# MASTER.net
KiCad netlist of a schematic drawn in Altium Designer
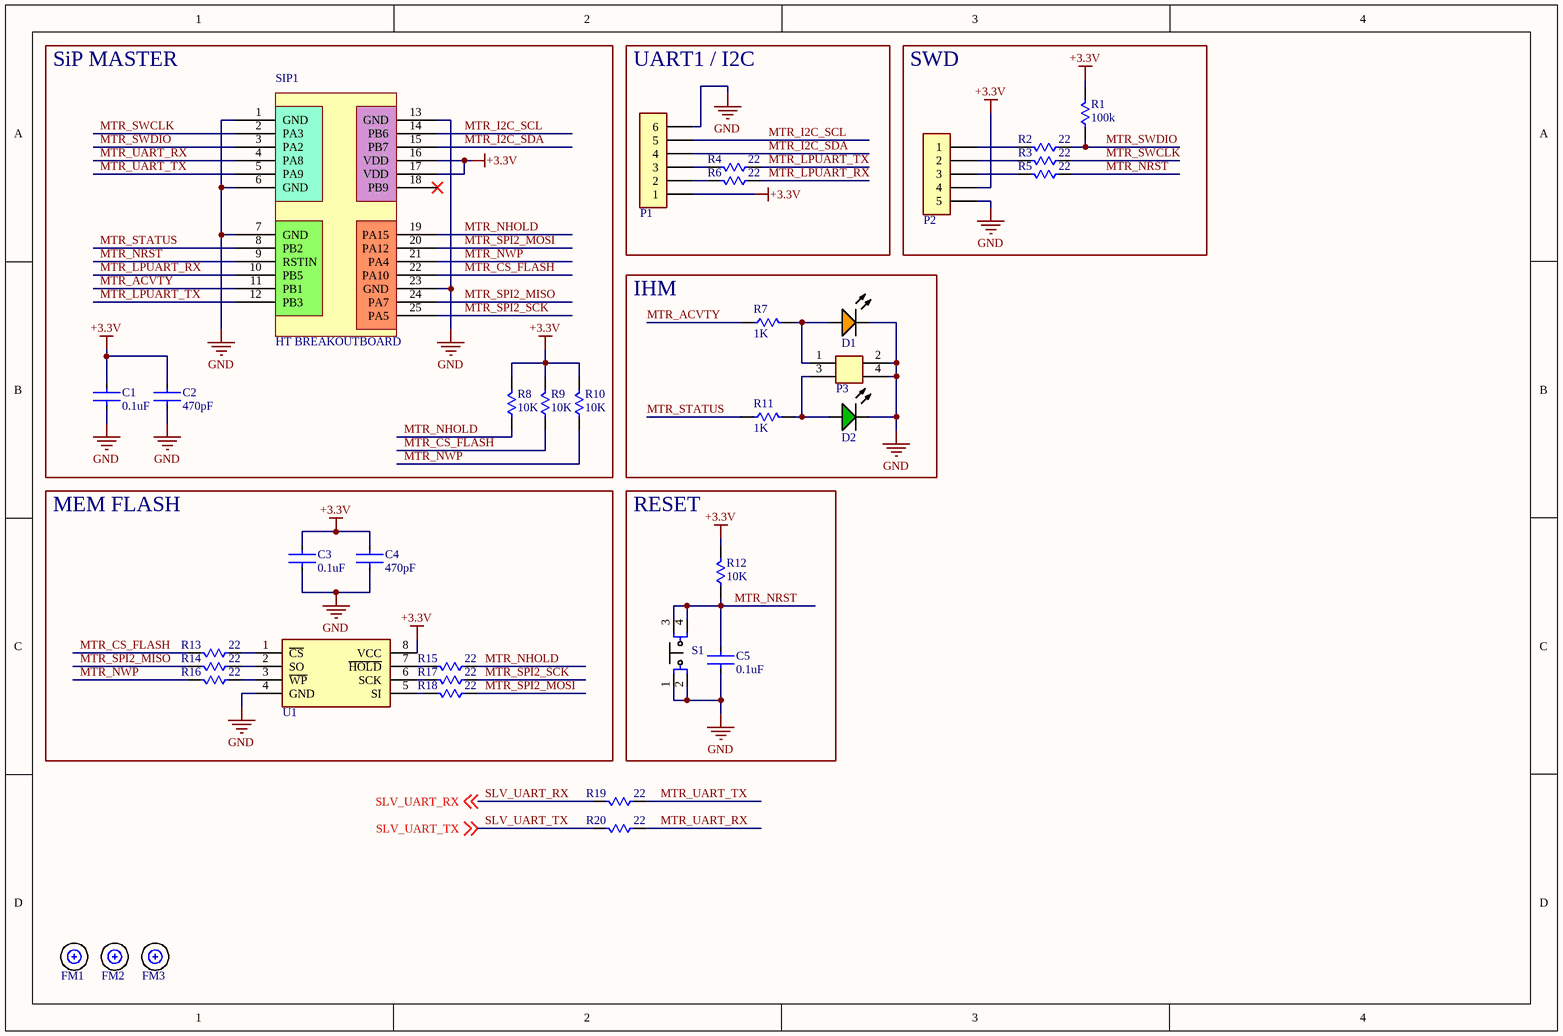
[diagram p0: MASTER.SchDoc]

(export (version "E")
  (design (tool "Eeschema 10.0.6"))
  (components
    (comp (ref "C1")
      (value "0.1uF")
      (footprint "0805-CAP")
      (description "CAP CER SMD 0805, 0.1uF / 16V, ±10%")
      (fields
        (field (name "MANUFACTURER") "Yageo")
        (field (name "MANUFACTURER PART NUMBER") "AC0805KRX7R7BB104")
      )
      (libsource (lib "Capacitor") (part "AC0805KRX7R7BB104"))
    )
    (comp (ref "C2")
      (value "470pF")
      (footprint "0805-CAP")
      (description "CAP CER SMD 0805, 470pF / 100V, ±5% C0G/NP0")
      (fields
        (field (name "MANUFACTURER") "Wurth Electronics")
        (field (name "MANUFACTURER PART NUMBER") "885012007086")
      )
      (libsource (lib "Capacitor") (part "885012007086"))
    )
    (comp (ref "C3")
      (value "0.1uF")
      (footprint "0805-CAP")
      (description "CAP CER SMD 0805, 0.1uF / 16V, ±10%")
      (fields
        (field (name "MANUFACTURER") "Yageo")
        (field (name "MANUFACTURER PART NUMBER") "AC0805KRX7R7BB104")
      )
      (libsource (lib "Capacitor") (part "AC0805KRX7R7BB104"))
    )
    (comp (ref "C4")
      (value "470pF")
      (footprint "0805-CAP")
      (description "CAP CER SMD 0805, 470pF / 100V, ±5% C0G/NP0")
      (fields
        (field (name "MANUFACTURER") "Wurth Electronics")
        (field (name "MANUFACTURER PART NUMBER") "885012007086")
      )
      (libsource (lib "Capacitor") (part "885012007086"))
    )
    (comp (ref "C5")
      (value "0.1uF")
      (footprint "0805-CAP")
      (description "CAP CER SMD 0805, 0.1uF / 16V, ±10%")
      (fields
        (field (name "MANUFACTURER") "Yageo")
        (field (name "MANUFACTURER PART NUMBER") "AC0805KRX7R7BB104")
      )
      (libsource (lib "Capacitor") (part "AC0805KRX7R7BB104"))
    )
    (comp (ref "D1")
      (value "ORANGE")
      (footprint "0805-LED-ORANGE")
      (description "LED ORANGE, SMD 0805, 2.1V/30mA")
      (fields
        (field (name "MANUFACTURER") "Vishay Lite-On")
        (field (name "MANUFACTURER PART NUMBER") "LTST-C170AKT")
      )
      (libsource (lib "Diode") (part "LTST-C170AKT"))
    )
    (comp (ref "D2")
      (value "GREEN")
      (footprint "0805-LED-GREEN")
      (description "LED GREEN, SMD 0805, 2.1V/30mA")
      (fields
        (field (name "MANUFACTURER") "Vishay Lite-On")
        (field (name "MANUFACTURER PART NUMBER") "LTST-C170GKT")
      )
      (libsource (lib "Diode") (part "LTST-C170GKT"))
    )
    (comp (ref "FM1")
      (value "FIDUCIAIS - SMD - POINT")
      (footprint "FIDUCIAL  1mm SMD")
      (libsource (lib "Connector") (part "FIDUCIAIS - SMD - POINT"))
    )
    (comp (ref "FM2")
      (value "FIDUCIAIS - SMD - POINT")
      (footprint "FIDUCIAL  1mm SMD")
      (libsource (lib "Connector") (part "FIDUCIAIS - SMD - POINT"))
    )
    (comp (ref "FM3")
      (value "FIDUCIAIS - SMD - POINT")
      (footprint "FIDUCIAL  1mm SMD")
      (libsource (lib "Connector") (part "FIDUCIAIS - SMD - POINT"))
    )
    (comp (ref "P1")
      (value "75915-306LF")
      (footprint "HEADER_6P_PVF - 75915-306LF")
      (fields (field (name "MANUFACTURER") "Amphenol ICC / FCI"))
      (libsource (lib "Connector") (part "75915-306LF"))
    )
    (comp (ref "P2")
      (value "Header 6")
      (footprint "_HEADER_5P_PVF")
      (fields
        (field (name "MANUFACTURER") "Amphenol ICC / FCI")
        (field (name "MANUFACTURER PART NUMBER") "75915-305LF")
      )
      (libsource (lib "Connector") (part "75915-305LF"))
    )
    (comp (ref "P3")
      (value "_HEADER_2X2_PVM_2.54MM")
      (footprint "67997-404HLF")
      (description "HEADER 2X3, PTH-2.54MM, VERT, MALE")
      (libsource (lib "Connector") (part "_HEADER_2X2_PVM_2.54MM"))
    )
    (comp (ref "R1")
      (value "100k")
      (footprint "0805-RES")
      (description "RES SMD 0805, 100K OHM 5% 1/8W")
      (fields
        (field (name "MANUFACTURER") "Panasonic")
        (field (name "MANUFACTURER PART NUMBER") "ERJ-6GEYJ104V")
      )
      (libsource (lib "Resistor") (part "ERJ-6GEYJ104V"))
    )
    (comp (ref "R2")
      (value "22")
      (footprint "0805-RES")
      (description "RES SMD 0805, 22 OHM 5% 1/4W")
      (fields
        (field (name "MANUFACTURER") "Panasonic")
        (field (name "MANUFACTURER PART NUMBER") "ERJ-P06J220V")
      )
      (libsource (lib "Resistor") (part "ERJ-P06J220V"))
    )
    (comp (ref "R3")
      (value "22")
      (footprint "0805-RES")
      (description "RES SMD 0805, 22 OHM 5% 1/4W")
      (fields
        (field (name "MANUFACTURER") "Panasonic")
        (field (name "MANUFACTURER PART NUMBER") "ERJ-P06J220V")
      )
      (libsource (lib "Resistor") (part "ERJ-P06J220V"))
    )
    (comp (ref "R4")
      (value "22")
      (footprint "0805-RES")
      (description "RES SMD 0805, 22 OHM 5% 1/4W")
      (fields
        (field (name "MANUFACTURER") "Panasonic")
        (field (name "MANUFACTURER PART NUMBER") "ERJ-P06J220V")
      )
      (libsource (lib "Resistor") (part "ERJ-P06J220V"))
    )
    (comp (ref "R5")
      (value "22")
      (footprint "0805-RES")
      (description "RES SMD 0805, 22 OHM 5% 1/4W")
      (fields
        (field (name "MANUFACTURER") "Panasonic")
        (field (name "MANUFACTURER PART NUMBER") "ERJ-P06J220V")
      )
      (libsource (lib "Resistor") (part "ERJ-P06J220V"))
    )
    (comp (ref "R6")
      (value "22")
      (footprint "0805-RES")
      (description "RES SMD 0805, 22 OHM 5% 1/4W")
      (fields
        (field (name "MANUFACTURER") "Panasonic")
        (field (name "MANUFACTURER PART NUMBER") "ERJ-P06J220V")
      )
      (libsource (lib "Resistor") (part "ERJ-P06J220V"))
    )
    (comp (ref "R7")
      (value "1K")
      (footprint "0805-RES")
      (description "Res Thin Film 0805 1K Ohm 1% 0.25W(1/4W) ±100ppm/C Sulfur Resistant Pad SMD T/R")
      (fields
        (field (name "MANUFACTURER") "Stackpole Electronics")
        (field (name "MANUFACTURER PART NUMBER") "RNCP0805FTD1K00")
      )
      (libsource (lib "Resistor") (part "RNCP0805FTD1K00"))
    )
    (comp (ref "R8")
      (value "10K")
      (footprint "0805-RES")
      (description "Res Thin Film 0805 10K Ohm 1% 1/4W ±100ppm/°C Molded SMD Paper T/R")
      (fields
        (field (name "MANUFACTURER") "Stackpole Electronics")
        (field (name "MANUFACTURER PART NUMBER") "RNCP0805FTD10K0")
      )
      (libsource (lib "Resistor") (part "RNCP0805FTD10K0"))
    )
    (comp (ref "R9")
      (value "10K")
      (footprint "0805-RES")
      (description "Res Thin Film 0805 10K Ohm 1% 1/4W ±100ppm/°C Molded SMD Paper T/R")
      (fields
        (field (name "MANUFACTURER") "Stackpole Electronics")
        (field (name "MANUFACTURER PART NUMBER") "RNCP0805FTD10K0")
      )
      (libsource (lib "Resistor") (part "RNCP0805FTD10K0"))
    )
    (comp (ref "R10")
      (value "10K")
      (footprint "0805-RES")
      (description "Res Thin Film 0805 10K Ohm 1% 1/4W ±100ppm/°C Molded SMD Paper T/R")
      (fields
        (field (name "MANUFACTURER") "Stackpole Electronics")
        (field (name "MANUFACTURER PART NUMBER") "RNCP0805FTD10K0")
      )
      (libsource (lib "Resistor") (part "RNCP0805FTD10K0"))
    )
    (comp (ref "R11")
      (value "1K")
      (footprint "0805-RES")
      (description "Res Thin Film 0805 1K Ohm 1% 0.25W(1/4W) ±100ppm/C Sulfur Resistant Pad SMD T/R")
      (fields
        (field (name "MANUFACTURER") "Stackpole Electronics")
        (field (name "MANUFACTURER PART NUMBER") "RNCP0805FTD1K00")
      )
      (libsource (lib "Resistor") (part "RNCP0805FTD1K00"))
    )
    (comp (ref "R12")
      (value "10K")
      (footprint "0805-RES")
      (description "Res Thin Film 0805 10K Ohm 1% 1/4W ±100ppm/°C Molded SMD Paper T/R")
      (fields
        (field (name "MANUFACTURER") "Stackpole Electronics")
        (field (name "MANUFACTURER PART NUMBER") "RNCP0805FTD10K0")
      )
      (libsource (lib "Resistor") (part "RNCP0805FTD10K0"))
    )
    (comp (ref "R13")
      (value "22")
      (footprint "0805-RES")
      (description "RES SMD 0805, 22 OHM 5% 1/4W")
      (fields
        (field (name "MANUFACTURER") "Panasonic")
        (field (name "MANUFACTURER PART NUMBER") "ERJ-P06J220V")
      )
      (libsource (lib "Resistor") (part "ERJ-P06J220V"))
    )
    (comp (ref "R14")
      (value "22")
      (footprint "0805-RES")
      (description "RES SMD 0805, 22 OHM 5% 1/4W")
      (fields
        (field (name "MANUFACTURER") "Panasonic")
        (field (name "MANUFACTURER PART NUMBER") "ERJ-P06J220V")
      )
      (libsource (lib "Resistor") (part "ERJ-P06J220V"))
    )
    (comp (ref "R15")
      (value "22")
      (footprint "0805-RES")
      (description "RES SMD 0805, 22 OHM 5% 1/4W")
      (fields
        (field (name "MANUFACTURER") "Panasonic")
        (field (name "MANUFACTURER PART NUMBER") "ERJ-P06J220V")
      )
      (libsource (lib "Resistor") (part "ERJ-P06J220V"))
    )
    (comp (ref "R16")
      (value "22")
      (footprint "0805-RES")
      (description "RES SMD 0805, 22 OHM 5% 1/4W")
      (fields
        (field (name "MANUFACTURER") "Panasonic")
        (field (name "MANUFACTURER PART NUMBER") "ERJ-P06J220V")
      )
      (libsource (lib "Resistor") (part "ERJ-P06J220V"))
    )
    (comp (ref "R17")
      (value "22")
      (footprint "0805-RES")
      (description "RES SMD 0805, 22 OHM 5% 1/4W")
      (fields
        (field (name "MANUFACTURER") "Panasonic")
        (field (name "MANUFACTURER PART NUMBER") "ERJ-P06J220V")
      )
      (libsource (lib "Resistor") (part "ERJ-P06J220V"))
    )
    (comp (ref "R18")
      (value "22")
      (footprint "0805-RES")
      (description "RES SMD 0805, 22 OHM 5% 1/4W")
      (fields
        (field (name "MANUFACTURER") "Panasonic")
        (field (name "MANUFACTURER PART NUMBER") "ERJ-P06J220V")
      )
      (libsource (lib "Resistor") (part "ERJ-P06J220V"))
    )
    (comp (ref "R19")
      (value "22")
      (footprint "0805-RES")
      (description "RES SMD 0805, 22 OHM 5% 1/4W")
      (fields
        (field (name "MANUFACTURER") "Panasonic")
        (field (name "MANUFACTURER PART NUMBER") "ERJ-P06J220V")
      )
      (libsource (lib "Resistor") (part "ERJ-P06J220V"))
    )
    (comp (ref "R20")
      (value "22")
      (footprint "0805-RES")
      (description "RES SMD 0805, 22 OHM 5% 1/4W")
      (fields
        (field (name "MANUFACTURER") "Panasonic")
        (field (name "MANUFACTURER PART NUMBER") "ERJ-P06J220V")
      )
      (libsource (lib "Resistor") (part "ERJ-P06J220V"))
    )
    (comp (ref "S1")
      (value "EVQ-P7A01P")
      (footprint "EVQP7A")
      (description "Switch Tactile N.O. SPST Rectangular Button Gull Wing 0.05A 12VDC 2.2N SMD Embossed T/R")
      (fields (field (name "MANUFACTURER") "Panasonic"))
      (libsource (lib "Switches") (part "EVQ-P7A01P"))
    )
    (comp (ref "SIP1")
      (value "HT BREAKOUTBOARD")
      (footprint "HT BREAKOUTBOARD PINS")
      (description "Pinos Fêmea para encaixe de HT Breakout")
      (libsource (lib "Connector") (part "HT BREAKOUTBOARD"))
    )
    (comp (ref "U1")
      (value "W25Q80DVSNIG")
      (footprint "SOIC-8")
      (description "IC FLASH 8MBIT 104MHZ 8SOIC")
      (fields (field (name "MANUFACTURER") "Winbond"))
      (libsource (lib "IC") (part "W25Q80DVSNIG"))
    )
  )
  (nets
    (net (code "1") (name "+3.3V") (class "Default")
      (node (ref "C1") (pin "1") (pinfunction "1_1") (pintype "passive"))
      (node (ref "C2") (pin "1") (pinfunction "1_1") (pintype "passive"))
      (node (ref "C3") (pin "1") (pinfunction "1_1") (pintype "passive"))
      (node (ref "C4") (pin "1") (pinfunction "1_1") (pintype "passive"))
      (node (ref "P1") (pin "1") (pinfunction "1_1") (pintype "passive"))
      (node (ref "P2") (pin "4") (pinfunction "4_4") (pintype "passive"))
      (node (ref "R1") (pin "2") (pinfunction "2_2") (pintype "passive"))
      (node (ref "R10") (pin "2") (pinfunction "2_2") (pintype "passive"))
      (node (ref "R12") (pin "2") (pinfunction "2_2") (pintype "passive"))
      (node (ref "R8") (pin "2") (pinfunction "2_2") (pintype "passive"))
      (node (ref "R9") (pin "2") (pinfunction "2_2") (pintype "passive"))
      (node (ref "SIP1") (pin "16") (pinfunction "VDD_16") (pintype "passive"))
      (node (ref "SIP1") (pin "17") (pinfunction "VDD_17") (pintype "passive"))
      (node (ref "U1") (pin "8") (pinfunction "VCC_8") (pintype "passive"))
    )
    (net (code "2") (name "/MTR_ACVTY") (class "Default")
      (node (ref "R7") (pin "1") (pinfunction "1_1") (pintype "passive"))
      (node (ref "SIP1") (pin "11") (pinfunction "PB1_11") (pintype "passive"))
    )
    (net (code "3") (name "/MTR_CS_FLASH") (class "Default")
      (node (ref "R13") (pin "2") (pinfunction "2_2") (pintype "passive"))
      (node (ref "R9") (pin "1") (pinfunction "1_1") (pintype "passive"))
      (node (ref "SIP1") (pin "22") (pinfunction "PA10_22") (pintype "passive"))
    )
    (net (code "4") (name "/MTR_I2C_SCL") (class "Default")
      (node (ref "P1") (pin "5") (pinfunction "5_5") (pintype "passive"))
      (node (ref "SIP1") (pin "14") (pinfunction "PB6_14") (pintype "passive"))
    )
    (net (code "5") (name "/MTR_I2C_SDA") (class "Default")
      (node (ref "P1") (pin "4") (pinfunction "4_4") (pintype "passive"))
      (node (ref "SIP1") (pin "15") (pinfunction "PB7_15") (pintype "passive"))
    )
    (net (code "6") (name "/MTR_LPUART_RX") (class "Default")
      (node (ref "R6") (pin "1") (pinfunction "1_1") (pintype "passive"))
      (node (ref "SIP1") (pin "10") (pinfunction "PB5_10") (pintype "passive"))
    )
    (net (code "7") (name "/MTR_LPUART_TX") (class "Default")
      (node (ref "R4") (pin "1") (pinfunction "1_1") (pintype "passive"))
      (node (ref "SIP1") (pin "12") (pinfunction "PB3_12") (pintype "passive"))
    )
    (net (code "8") (name "/MTR_NHOLD") (class "Default")
      (node (ref "R15") (pin "1") (pinfunction "1_1") (pintype "passive"))
      (node (ref "R8") (pin "1") (pinfunction "1_1") (pintype "passive"))
      (node (ref "SIP1") (pin "19") (pinfunction "PA15_19") (pintype "passive"))
    )
    (net (code "9") (name "/MTR_NRST") (class "Default")
      (node (ref "C5") (pin "1") (pinfunction "1_1") (pintype "passive"))
      (node (ref "R12") (pin "1") (pinfunction "1_1") (pintype "passive"))
      (node (ref "R5") (pin "1") (pinfunction "1_1") (pintype "passive"))
      (node (ref "S1") (pin "3") (pinfunction "3_3") (pintype "passive"))
      (node (ref "S1") (pin "4") (pinfunction "4_4") (pintype "passive"))
      (node (ref "SIP1") (pin "9") (pinfunction "RSTIN_9") (pintype "passive"))
    )
    (net (code "10") (name "/MTR_NWP") (class "Default")
      (node (ref "R10") (pin "1") (pinfunction "1_1") (pintype "passive"))
      (node (ref "R16") (pin "2") (pinfunction "2_2") (pintype "passive"))
      (node (ref "SIP1") (pin "21") (pinfunction "PA4_21") (pintype "passive"))
    )
    (net (code "11") (name "/MTR_SPI2_MISO") (class "Default")
      (node (ref "R14") (pin "2") (pinfunction "2_2") (pintype "passive"))
      (node (ref "SIP1") (pin "24") (pinfunction "PA7_24") (pintype "passive"))
    )
    (net (code "12") (name "/MTR_SPI2_MOSI") (class "Default")
      (node (ref "R18") (pin "1") (pinfunction "1_1") (pintype "passive"))
      (node (ref "SIP1") (pin "20") (pinfunction "PA12_20") (pintype "passive"))
    )
    (net (code "13") (name "/MTR_SPI2_SCK") (class "Default")
      (node (ref "R17") (pin "1") (pinfunction "1_1") (pintype "passive"))
      (node (ref "SIP1") (pin "25") (pinfunction "PA5_25") (pintype "passive"))
    )
    (net (code "14") (name "/MTR_STATUS") (class "Default")
      (node (ref "R11") (pin "1") (pinfunction "1_1") (pintype "passive"))
      (node (ref "SIP1") (pin "8") (pinfunction "PB2_8") (pintype "passive"))
    )
    (net (code "15") (name "/MTR_SWCLK") (class "Default")
      (node (ref "R3") (pin "1") (pinfunction "1_1") (pintype "passive"))
      (node (ref "SIP1") (pin "2") (pinfunction "PA3_2") (pintype "passive"))
    )
    (net (code "16") (name "/MTR_SWDIO") (class "Default")
      (node (ref "R1") (pin "1") (pinfunction "1_1") (pintype "passive"))
      (node (ref "R2") (pin "1") (pinfunction "1_1") (pintype "passive"))
      (node (ref "SIP1") (pin "3") (pinfunction "PA2_3") (pintype "passive"))
    )
    (net (code "17") (name "/MTR_UART_RX") (class "Default")
      (node (ref "R20") (pin "1") (pinfunction "1_1") (pintype "passive"))
      (node (ref "SIP1") (pin "4") (pinfunction "PA8_4") (pintype "passive"))
    )
    (net (code "18") (name "/MTR_UART_TX") (class "Default")
      (node (ref "R19") (pin "1") (pinfunction "1_1") (pintype "passive"))
      (node (ref "SIP1") (pin "5") (pinfunction "PA9_5") (pintype "passive"))
    )
    (net (code "19") (name "GND") (class "Default")
      (node (ref "C1") (pin "2") (pinfunction "2_2") (pintype "passive"))
      (node (ref "C2") (pin "2") (pinfunction "2_2") (pintype "passive"))
      (node (ref "C3") (pin "2") (pinfunction "2_2") (pintype "passive"))
      (node (ref "C4") (pin "2") (pinfunction "2_2") (pintype "passive"))
      (node (ref "C5") (pin "2") (pinfunction "2_2") (pintype "passive"))
      (node (ref "D1") (pin "2") (pinfunction "K_2") (pintype "passive"))
      (node (ref "D2") (pin "2") (pinfunction "K_2") (pintype "passive"))
      (node (ref "P1") (pin "6") (pinfunction "6_6") (pintype "passive"))
      (node (ref "P2") (pin "5") (pinfunction "5_5") (pintype "passive"))
      (node (ref "P3") (pin "2") (pinfunction "2_2") (pintype "passive"))
      (node (ref "P3") (pin "4") (pinfunction "4_4") (pintype "passive"))
      (node (ref "S1") (pin "1") (pinfunction "1_1") (pintype "passive"))
      (node (ref "S1") (pin "2") (pinfunction "2_2") (pintype "passive"))
      (node (ref "SIP1") (pin "1") (pinfunction "GND_1") (pintype "passive"))
      (node (ref "SIP1") (pin "13") (pinfunction "GND_13") (pintype "passive"))
      (node (ref "SIP1") (pin "23") (pinfunction "GND_23") (pintype "passive"))
      (node (ref "SIP1") (pin "6") (pinfunction "GND_6") (pintype "passive"))
      (node (ref "SIP1") (pin "7") (pinfunction "GND_7") (pintype "passive"))
      (node (ref "U1") (pin "4") (pinfunction "GND_4") (pintype "passive"))
    )
    (net (code "20") (name "Net-(D1-A)") (class "Default")
      (node (ref "D1") (pin "1") (pinfunction "A_1") (pintype "passive"))
      (node (ref "P3") (pin "1") (pinfunction "1_1") (pintype "passive"))
      (node (ref "R7") (pin "2") (pinfunction "2_2") (pintype "passive"))
    )
    (net (code "21") (name "Net-(D2-A)") (class "Default")
      (node (ref "D2") (pin "1") (pinfunction "A_1") (pintype "passive"))
      (node (ref "P3") (pin "3") (pinfunction "3_3") (pintype "passive"))
      (node (ref "R11") (pin "2") (pinfunction "2_2") (pintype "passive"))
    )
    (net (code "22") (name "Net-(P1-Pad2)") (class "Default")
      (node (ref "P1") (pin "2") (pinfunction "2_2") (pintype "passive"))
      (node (ref "R6") (pin "2") (pinfunction "2_2") (pintype "passive"))
    )
    (net (code "23") (name "Net-(P1-Pad3)") (class "Default")
      (node (ref "P1") (pin "3") (pinfunction "3_3") (pintype "passive"))
      (node (ref "R4") (pin "2") (pinfunction "2_2") (pintype "passive"))
    )
    (net (code "24") (name "Net-(P2-Pad1)") (class "Default")
      (node (ref "P2") (pin "1") (pinfunction "1_1") (pintype "passive"))
      (node (ref "R2") (pin "2") (pinfunction "2_2") (pintype "passive"))
    )
    (net (code "25") (name "Net-(P2-Pad2)") (class "Default")
      (node (ref "P2") (pin "2") (pinfunction "2_2") (pintype "passive"))
      (node (ref "R3") (pin "2") (pinfunction "2_2") (pintype "passive"))
    )
    (net (code "26") (name "Net-(P2-Pad3)") (class "Default")
      (node (ref "P2") (pin "3") (pinfunction "3_3") (pintype "passive"))
      (node (ref "R5") (pin "2") (pinfunction "2_2") (pintype "passive"))
    )
    (net (code "27") (name "Net-(U1-SCK)") (class "Default")
      (node (ref "R17") (pin "2") (pinfunction "2_2") (pintype "passive"))
      (node (ref "U1") (pin "6") (pinfunction "SCK_6") (pintype "passive"))
    )
    (net (code "28") (name "Net-(U1-SI)") (class "Default")
      (node (ref "R18") (pin "2") (pinfunction "2_2") (pintype "passive"))
      (node (ref "U1") (pin "5") (pinfunction "SI_5") (pintype "passive"))
    )
    (net (code "29") (name "Net-(U1-SO)") (class "Default")
      (node (ref "R14") (pin "1") (pinfunction "1_1") (pintype "passive"))
      (node (ref "U1") (pin "2") (pinfunction "SO_2") (pintype "passive"))
    )
    (net (code "30") (name "Net-(U1-~{CS})") (class "Default")
      (node (ref "R13") (pin "1") (pinfunction "1_1") (pintype "passive"))
      (node (ref "U1") (pin "1") (pinfunction "~{CS}_1") (pintype "passive"))
    )
    (net (code "31") (name "Net-(U1-~{HOLD})") (class "Default")
      (node (ref "R15") (pin "2") (pinfunction "2_2") (pintype "passive"))
      (node (ref "U1") (pin "7") (pinfunction "~{HOLD}_7") (pintype "passive"))
    )
    (net (code "32") (name "Net-(U1-~{WP})") (class "Default")
      (node (ref "R16") (pin "1") (pinfunction "1_1") (pintype "passive"))
      (node (ref "U1") (pin "3") (pinfunction "~{WP}_3") (pintype "passive"))
    )
    (net (code "33") (name "SLV_UART_RX") (class "Default")
      (node (ref "R19") (pin "2") (pinfunction "2_2") (pintype "passive"))
    )
    (net (code "34") (name "SLV_UART_TX") (class "Default")
      (node (ref "R20") (pin "2") (pinfunction "2_2") (pintype "passive"))
    )
    (net (code "35") (name "unconnected-(FM1-Pad1)") (class "Default")
      (node (ref "FM1") (pin "1") (pinfunction "1_1") (pintype "passive"))
    )
    (net (code "36") (name "unconnected-(FM2-Pad1)") (class "Default")
      (node (ref "FM2") (pin "1") (pinfunction "1_1") (pintype "passive"))
    )
    (net (code "37") (name "unconnected-(FM3-Pad1)") (class "Default")
      (node (ref "FM3") (pin "1") (pinfunction "1_1") (pintype "passive"))
    )
    (net (code "38") (name "unconnected-(SIP1-PB9-Pad18)") (class "Default")
      (node (ref "SIP1") (pin "18") (pinfunction "PB9_18") (pintype "passive+no_connect"))
    )
  )
)
